# SCH_Hackathon_2025-03-07.net
KiCad netlist of a schematic drawn in EasyEDA
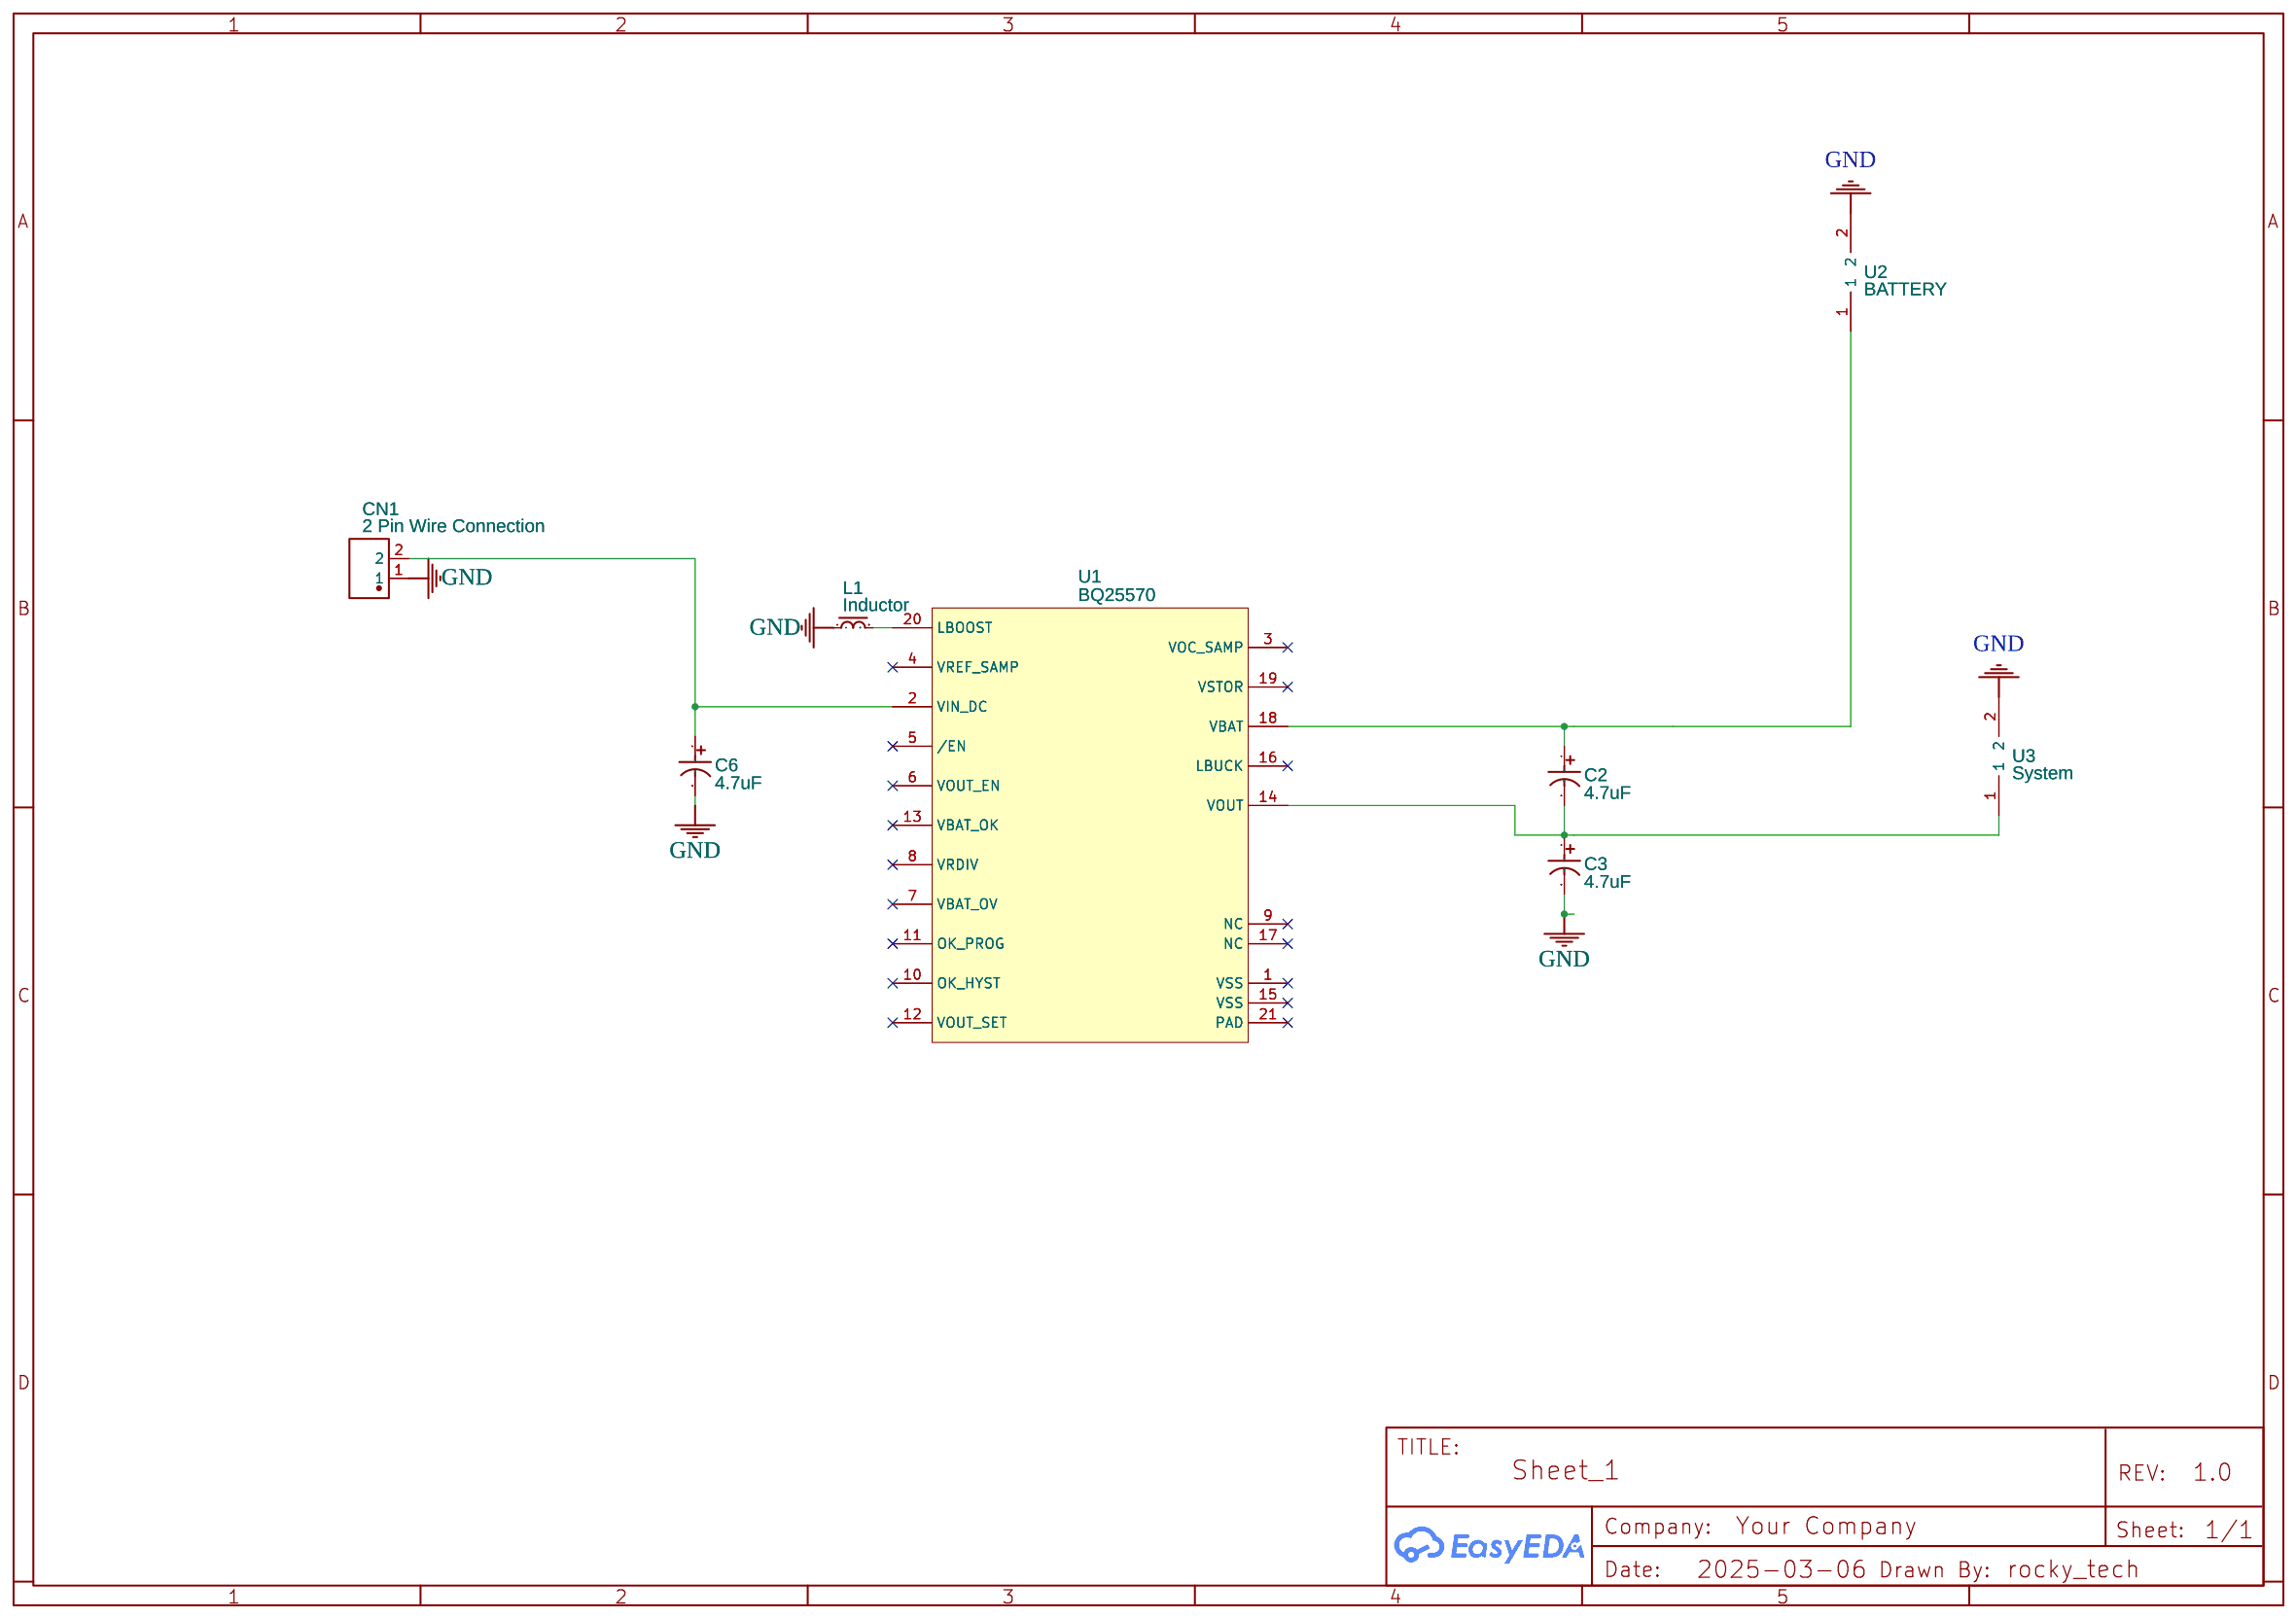
[diagram p0: schematic sheet]

(export (version "E")
  (design (tool "Eeschema 10.0.6"))
  (components
    (comp (ref "C2")
      (value "4.7uF")
      (fields
        (field (name "Manufacturer Part") "KM475M250F12RR0VH2FP0")
        (field (name "Manufacturer") "CX(承兴)")
      )
      (libsource (lib "") (part "250V 4.7uF 8X12"))
    )
    (comp (ref "C3")
      (value "4.7uF")
      (fields
        (field (name "Manufacturer Part") "KM475M250F12RR0VH2FP0")
        (field (name "Manufacturer") "CX(承兴)")
      )
      (libsource (lib "") (part "250V 4.7uF 8X12"))
    )
    (comp (ref "C6")
      (value "4.7uF")
      (fields
        (field (name "Manufacturer Part") "KM475M250F12RR0VH2FP0")
        (field (name "Manufacturer") "CX(承兴)")
      )
      (libsource (lib "") (part "250V 4.7uF 8X12"))
    )
    (comp (ref "CN1") (value "2 Pin Wire Connection") (libsource (lib "") (part "2 Pin Wire Connection")))
    (comp (ref "L1") (value "Inductor") (libsource (lib "") (part "Inductor")))
    (comp (ref "U1")
      (value "BQ25570")
      (fields (field (name "Manufacturer") "Texas Instruments"))
      (libsource (lib "") (part "BQ25570"))
    )
    (comp (ref "U2") (value "BATTERY") (libsource (lib "") (part "2.54 mm 2x1 THT male pin header")))
    (comp (ref "U3") (value "System") (libsource (lib "") (part "2.54 mm 2x1 THT male pin header")))
  )
  (nets
    (net (code "1") (name "GND") (class "Default")
      (node (ref "C3") (pin "2") (pinfunction "2_2") (pintype "input"))
      (node (ref "C6") (pin "2") (pinfunction "2_2") (pintype "input"))
      (node (ref "CN1") (pin "1") (pinfunction "1_1") (pintype "unspecified"))
      (node (ref "L1") (pin "1") (pinfunction "1_1") (pintype "unspecified"))
      (node (ref "U2") (pin "2") (pinfunction "2_2") (pintype "unspecified"))
      (node (ref "U3") (pin "2") (pinfunction "2_2") (pintype "unspecified"))
    )
    (net (code "2") (name "Net-(U1-LBOOST)") (class "Default")
      (node (ref "L1") (pin "2") (pinfunction "2_2") (pintype "unspecified"))
      (node (ref "U1") (pin "20") (pinfunction "LBOOST_20") (pintype "input"))
    )
    (net (code "3") (name "Net-(U1-VBAT)") (class "Default")
      (node (ref "C2") (pin "1") (pinfunction "1_1") (pintype "input"))
      (node (ref "U1") (pin "18") (pinfunction "VBAT_18") (pintype "bidirectional"))
      (node (ref "U2") (pin "1") (pinfunction "1_1") (pintype "unspecified"))
    )
    (net (code "4") (name "Net-(U1-VIN_DC)") (class "Default")
      (node (ref "C6") (pin "1") (pinfunction "1_1") (pintype "input"))
      (node (ref "CN1") (pin "2") (pinfunction "2_2") (pintype "unspecified"))
      (node (ref "U1") (pin "2") (pinfunction "VIN_DC_2") (pintype "unspecified"))
    )
    (net (code "5") (name "Net-(U1-VOUT)") (class "Default")
      (node (ref "C2") (pin "2") (pinfunction "2_2") (pintype "input"))
      (node (ref "C3") (pin "1") (pinfunction "1_1") (pintype "input"))
      (node (ref "U1") (pin "14") (pinfunction "VOUT_14") (pintype "unspecified"))
      (node (ref "U3") (pin "1") (pinfunction "1_1") (pintype "unspecified"))
    )
    (net (code "6") (name "unconnected-(U1-LBUCK-Pad16)") (class "Default")
      (node (ref "U1") (pin "16") (pinfunction "LBUCK_16") (pintype "unspecified+no_connect"))
    )
    (net (code "7") (name "unconnected-(U1-NC-Pad9)") (class "Default")
      (node (ref "U1") (pin "9") (pinfunction "NC_9") (pintype "unspecified+no_connect"))
    )
    (net (code "8") (name "unconnected-(U1-NC-Pad17)") (class "Default")
      (node (ref "U1") (pin "17") (pinfunction "NC_17") (pintype "unspecified+no_connect"))
    )
    (net (code "9") (name "unconnected-(U1-OK_HYST-Pad10)") (class "Default")
      (node (ref "U1") (pin "10") (pinfunction "OK_HYST_10") (pintype "input+no_connect"))
    )
    (net (code "10") (name "unconnected-(U1-OK_PROG-Pad11)") (class "Default")
      (node (ref "U1") (pin "11") (pinfunction "OK_PROG_11") (pintype "input+no_connect"))
    )
    (net (code "11") (name "unconnected-(U1-PAD-Pad21)") (class "Default")
      (node (ref "U1") (pin "21") (pinfunction "PAD_21") (pintype "unspecified+no_connect"))
    )
    (net (code "12") (name "unconnected-(U1-VBAT_OK-Pad13)") (class "Default")
      (node (ref "U1") (pin "13") (pinfunction "VBAT_OK_13") (pintype "output+no_connect"))
    )
    (net (code "13") (name "unconnected-(U1-VBAT_OV-Pad7)") (class "Default")
      (node (ref "U1") (pin "7") (pinfunction "VBAT_OV_7") (pintype "input+no_connect"))
    )
    (net (code "14") (name "unconnected-(U1-VOC_SAMP-Pad3)") (class "Default")
      (node (ref "U1") (pin "3") (pinfunction "VOC_SAMP_3") (pintype "input+no_connect"))
    )
    (net (code "15") (name "unconnected-(U1-VOUT_EN-Pad6)") (class "Default")
      (node (ref "U1") (pin "6") (pinfunction "VOUT_EN_6") (pintype "input+no_connect"))
    )
    (net (code "16") (name "unconnected-(U1-VOUT_SET-Pad12)") (class "Default")
      (node (ref "U1") (pin "12") (pinfunction "VOUT_SET_12") (pintype "input+no_connect"))
    )
    (net (code "17") (name "unconnected-(U1-VRDIV-Pad8)") (class "Default")
      (node (ref "U1") (pin "8") (pinfunction "VRDIV_8") (pintype "output+no_connect"))
    )
    (net (code "18") (name "unconnected-(U1-VREF_SAMP-Pad4)") (class "Default")
      (node (ref "U1") (pin "4") (pinfunction "VREF_SAMP_4") (pintype "input+no_connect"))
    )
    (net (code "19") (name "unconnected-(U1-VSS-Pad1)") (class "Default")
      (node (ref "U1") (pin "1") (pinfunction "VSS_1") (pintype "unspecified+no_connect"))
    )
    (net (code "20") (name "unconnected-(U1-VSS-Pad15)") (class "Default")
      (node (ref "U1") (pin "15") (pinfunction "VSS_15") (pintype "unspecified+no_connect"))
    )
    (net (code "21") (name "unconnected-(U1-VSTOR-Pad19)") (class "Default")
      (node (ref "U1") (pin "19") (pinfunction "VSTOR_19") (pintype "unspecified+no_connect"))
    )
    (net (code "22") (name "unconnected-(U1-{slash}EN-Pad5)") (class "Default")
      (node (ref "U1") (pin "5") (pinfunction "/EN_5") (pintype "input+no_connect"))
    )
  )
)
